# untitled_wifi.net
KiCad netlist of a schematic drawn in EAGLE
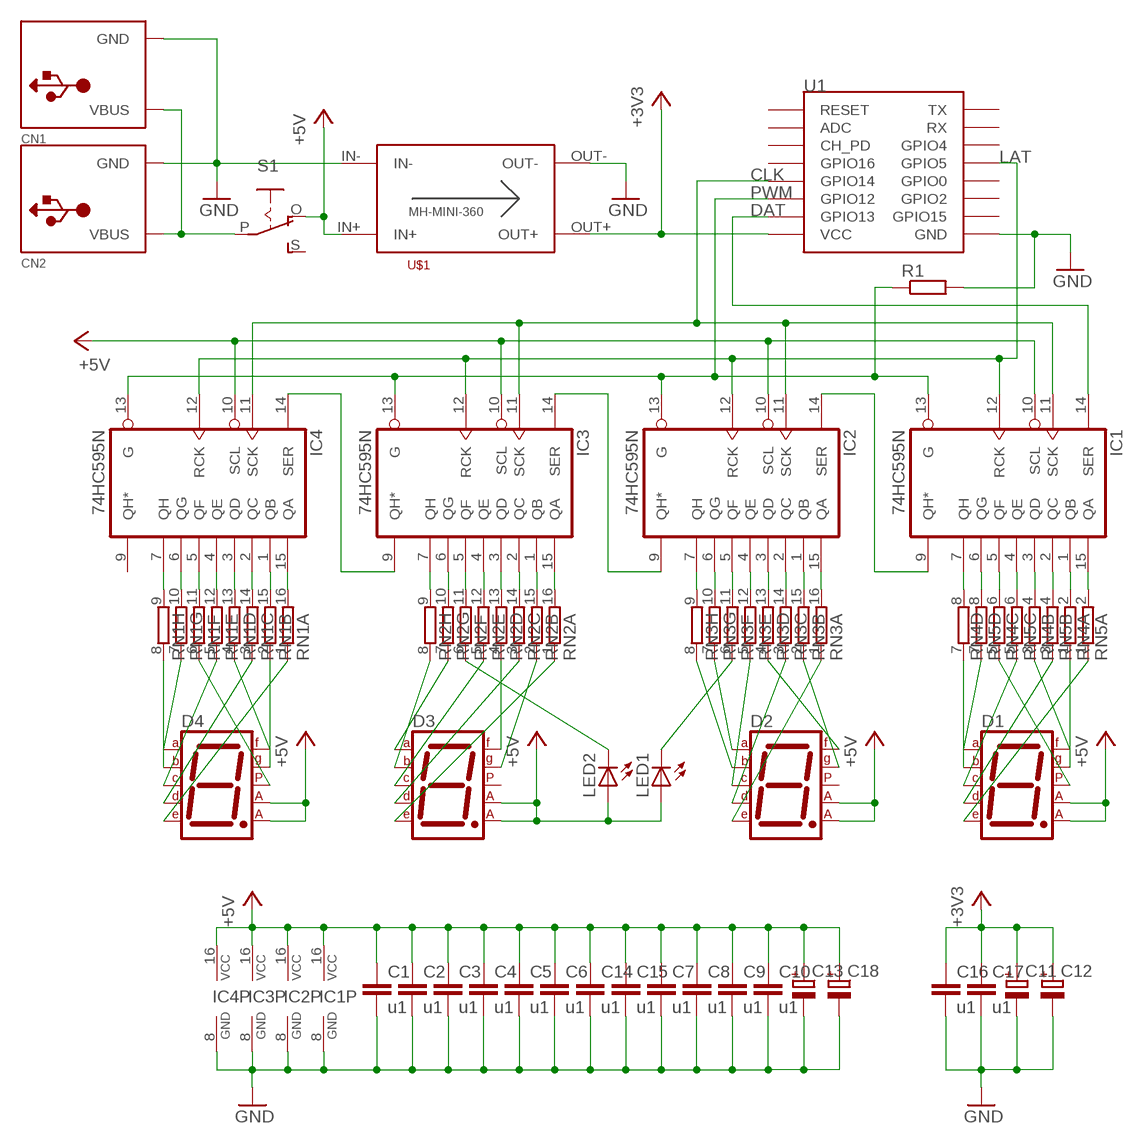
[diagram p0: schematic, sheet 1]

(export (version "E")
  (design (tool "Eeschema 10.0.6"))
  (components
    (comp (ref "C1")
      (value "u1")
      (footprint "eagle-import:C025-025X050")
      (libsource (lib "eagle-import") (part "C-EU025-025X050"))
    )
    (comp (ref "C2")
      (value "u1")
      (footprint "eagle-import:C025-025X050")
      (libsource (lib "eagle-import") (part "C-EU025-025X050"))
    )
    (comp (ref "C3")
      (value "u1")
      (footprint "eagle-import:C025-025X050")
      (libsource (lib "eagle-import") (part "C-EU025-025X050"))
    )
    (comp (ref "C4")
      (value "u1")
      (footprint "eagle-import:C025-025X050")
      (libsource (lib "eagle-import") (part "C-EU025-025X050"))
    )
    (comp (ref "C5")
      (value "u1")
      (footprint "eagle-import:C025-025X050")
      (libsource (lib "eagle-import") (part "C-EU025-025X050"))
    )
    (comp (ref "C6")
      (value "u1")
      (footprint "eagle-import:C025-025X050")
      (libsource (lib "eagle-import") (part "C-EU025-025X050"))
    )
    (comp (ref "C7")
      (value "u1")
      (footprint "eagle-import:C0805K")
      (libsource (lib "eagle-import") (part "C-EUC0805K"))
    )
    (comp (ref "C8")
      (value "u1")
      (footprint "eagle-import:C0805K")
      (libsource (lib "eagle-import") (part "C-EUC0805K"))
    )
    (comp (ref "C9")
      (value "u1")
      (footprint "eagle-import:C0805K")
      (libsource (lib "eagle-import") (part "C-EUC0805K"))
    )
    (comp (ref "C10")
      (value "u1")
      (footprint "eagle-import:C0805K")
      (libsource (lib "eagle-import") (part "C-EUC0805K"))
    )
    (comp (ref "C11")
      (value "CPOL-EUTT2D4L")
      (footprint "eagle-import:TT2D4L")
      (libsource (lib "eagle-import") (part "CPOL-EUTT2D4L"))
    )
    (comp (ref "C12")
      (value "CPOL-EUTT2D4L")
      (footprint "eagle-import:TT2D4L")
      (libsource (lib "eagle-import") (part "CPOL-EUTT2D4L"))
    )
    (comp (ref "C13")
      (value "CPOL-EUE2.5-7")
      (footprint "eagle-import:E2,5-7")
      (libsource (lib "eagle-import") (part "CPOL-EUE2.5-7"))
    )
    (comp (ref "C14")
      (value "u1")
      (footprint "eagle-import:C025-025X050")
      (libsource (lib "eagle-import") (part "C-EU025-025X050"))
    )
    (comp (ref "C15")
      (value "u1")
      (footprint "eagle-import:C025-025X050")
      (libsource (lib "eagle-import") (part "C-EU025-025X050"))
    )
    (comp (ref "C16")
      (value "u1")
      (footprint "eagle-import:C025-025X050")
      (libsource (lib "eagle-import") (part "C-EU025-025X050"))
    )
    (comp (ref "C17")
      (value "u1")
      (footprint "eagle-import:C025-025X050")
      (libsource (lib "eagle-import") (part "C-EU025-025X050"))
    )
    (comp (ref "C18")
      (value "CPOL-EUE2.5-7")
      (footprint "eagle-import:E2,5-7")
      (libsource (lib "eagle-import") (part "CPOL-EUE2.5-7"))
    )
    (comp (ref "CN1")
      (value "USBPWR-ONLY")
      (footprint "eagle-import:USB-MINIB-THM")
      (libsource (lib "eagle-import") (part "USBPWR-ONLY"))
    )
    (comp (ref "CN2")
      (value "USBPWR-ONLY")
      (footprint "eagle-import:USB-MINIB-THM")
      (libsource (lib "eagle-import") (part "USBPWR-ONLY"))
    )
    (comp (ref "D1")
      (value "7SEG-CA")
      (footprint "eagle-import:7SEG-13")
      (libsource (lib "eagle-import") (part "7SEG-CA"))
    )
    (comp (ref "D2")
      (value "7SEG-CA")
      (footprint "eagle-import:7SEG-13")
      (libsource (lib "eagle-import") (part "7SEG-CA"))
    )
    (comp (ref "D3")
      (value "7SEG-CA")
      (footprint "eagle-import:7SEG-13")
      (libsource (lib "eagle-import") (part "7SEG-CA"))
    )
    (comp (ref "D4")
      (value "7SEG-CA")
      (footprint "eagle-import:7SEG-13")
      (libsource (lib "eagle-import") (part "7SEG-CA"))
    )
    (comp (ref "IC1")
      (value "74HC595N")
      (footprint "eagle-import:DIL16")
      (libsource (lib "eagle-import") (part "74595NHC"))
    )
    (comp (ref "IC2")
      (value "74HC595N")
      (footprint "eagle-import:DIL16")
      (libsource (lib "eagle-import") (part "74595NHC"))
    )
    (comp (ref "IC3")
      (value "74HC595N")
      (footprint "eagle-import:DIL16")
      (libsource (lib "eagle-import") (part "74595NHC"))
    )
    (comp (ref "IC4")
      (value "74HC595N")
      (footprint "eagle-import:DIL16")
      (libsource (lib "eagle-import") (part "74595NHC"))
    )
    (comp (ref "LED1")
      (value "LED3MM")
      (footprint "eagle-import:LED3MM")
      (libsource (lib "eagle-import") (part "LED3MM"))
    )
    (comp (ref "LED2")
      (value "LED3MM")
      (footprint "eagle-import:LED3MM")
      (libsource (lib "eagle-import") (part "LED3MM"))
    )
    (comp (ref "R1")
      (value "R-EU_0204/7")
      (footprint "eagle-import:0204_7")
      (libsource (lib "eagle-import") (part "R-EU_0204/7"))
    )
    (comp (ref "RN1")
      (value "8R-N")
      (footprint "eagle-import:DIL16")
      (libsource (lib "eagle-import") (part "8R-N"))
    )
    (comp (ref "RN2")
      (value "8R-N")
      (footprint "eagle-import:DIL16")
      (libsource (lib "eagle-import") (part "8R-N"))
    )
    (comp (ref "RN3")
      (value "8R-N")
      (footprint "eagle-import:DIL16")
      (libsource (lib "eagle-import") (part "8R-N"))
    )
    (comp (ref "RN4")
      (value "E4R")
      (footprint "eagle-import:SIL8")
      (libsource (lib "eagle-import") (part "E4R"))
    )
    (comp (ref "RN5")
      (value "E4R")
      (footprint "eagle-import:SIL8")
      (libsource (lib "eagle-import") (part "E4R"))
    )
    (comp (ref "S1")
      (value "EG1218S")
      (footprint "eagle-import:EG1218")
      (libsource (lib "eagle-import") (part "EG1218S"))
    )
    (comp (ref "U$1")
      (value "DC-DC_CONV_MINISTD")
      (footprint "eagle-import:DC-DC_CONV_MINI")
      (libsource (lib "eagle-import") (part "DC-DC_CONV_MINISTD"))
    )
    (comp (ref "U1")
      (value "ESP12EDIP")
      (footprint "eagle-import:ESP-12-BREAKOUT")
      (libsource (lib "eagle-import") (part "ESP12EDIP"))
    )
  )
  (nets
    (net (code "1") (name "+3V3") (class "Default")
      (node (ref "C11") (pin "+") (pinfunction "+_+") (pintype "passive"))
      (node (ref "C12") (pin "+") (pinfunction "+_+") (pintype "passive"))
      (node (ref "C16") (pin "1") (pinfunction "1_1") (pintype "passive"))
      (node (ref "C17") (pin "1") (pinfunction "1_1") (pintype "passive"))
      (node (ref "U$1") (pin "OUT+") (pinfunction "OUT+_OUT+") (pintype "bidirectional"))
      (node (ref "U1") (pin "P$1") (pinfunction "VCC_P$1") (pintype "bidirectional"))
    )
    (net (code "2") (name "+5V") (class "Default")
      (node (ref "C1") (pin "1") (pinfunction "1_1") (pintype "passive"))
      (node (ref "C10") (pin "1") (pinfunction "1_1") (pintype "passive"))
      (node (ref "C13") (pin "+") (pinfunction "+_+") (pintype "passive"))
      (node (ref "C14") (pin "1") (pinfunction "1_1") (pintype "passive"))
      (node (ref "C15") (pin "1") (pinfunction "1_1") (pintype "passive"))
      (node (ref "C18") (pin "+") (pinfunction "+_+") (pintype "passive"))
      (node (ref "C2") (pin "1") (pinfunction "1_1") (pintype "passive"))
      (node (ref "C3") (pin "1") (pinfunction "1_1") (pintype "passive"))
      (node (ref "C4") (pin "1") (pinfunction "1_1") (pintype "passive"))
      (node (ref "C5") (pin "1") (pinfunction "1_1") (pintype "passive"))
      (node (ref "C6") (pin "1") (pinfunction "1_1") (pintype "passive"))
      (node (ref "C7") (pin "1") (pinfunction "1_1") (pintype "passive"))
      (node (ref "C8") (pin "1") (pinfunction "1_1") (pintype "passive"))
      (node (ref "C9") (pin "1") (pinfunction "1_1") (pintype "passive"))
      (node (ref "D1") (pin "3") (pinfunction "CA1_3") (pintype "passive"))
      (node (ref "D1") (pin "8") (pinfunction "CA2_8") (pintype "passive"))
      (node (ref "D2") (pin "3") (pinfunction "CA1_3") (pintype "passive"))
      (node (ref "D2") (pin "8") (pinfunction "CA2_8") (pintype "passive"))
      (node (ref "D3") (pin "3") (pinfunction "CA1_3") (pintype "passive"))
      (node (ref "D3") (pin "8") (pinfunction "CA2_8") (pintype "passive"))
      (node (ref "D4") (pin "3") (pinfunction "CA1_3") (pintype "passive"))
      (node (ref "D4") (pin "8") (pinfunction "CA2_8") (pintype "passive"))
      (node (ref "IC1") (pin "10") (pinfunction "SCL_10") (pintype "input"))
      (node (ref "IC1") (pin "16") (pinfunction "VCC_16") (pintype "power_in"))
      (node (ref "IC2") (pin "10") (pinfunction "SCL_10") (pintype "input"))
      (node (ref "IC2") (pin "16") (pinfunction "VCC_16") (pintype "power_in"))
      (node (ref "IC3") (pin "10") (pinfunction "SCL_10") (pintype "input"))
      (node (ref "IC3") (pin "16") (pinfunction "VCC_16") (pintype "power_in"))
      (node (ref "IC4") (pin "10") (pinfunction "SCL_10") (pintype "input"))
      (node (ref "IC4") (pin "16") (pinfunction "VCC_16") (pintype "power_in"))
      (node (ref "LED1") (pin "A") (pinfunction "A_A") (pintype "passive"))
      (node (ref "LED2") (pin "A") (pinfunction "A_A") (pintype "passive"))
      (node (ref "S1") (pin "O") (pinfunction "O_O") (pintype "passive"))
      (node (ref "U$1") (pin "IN+") (pinfunction "IN+_IN+") (pintype "bidirectional"))
    )
    (net (code "3") (name "/CLK") (class "Default")
      (node (ref "IC1") (pin "11") (pinfunction "SCK_11") (pintype "input"))
      (node (ref "IC2") (pin "11") (pinfunction "SCK_11") (pintype "input"))
      (node (ref "IC3") (pin "11") (pinfunction "SCK_11") (pintype "input"))
      (node (ref "IC4") (pin "11") (pinfunction "SCK_11") (pintype "input"))
      (node (ref "U1") (pin "P$4") (pinfunction "GPIO14_P$4") (pintype "bidirectional"))
    )
    (net (code "4") (name "/DAT") (class "Default")
      (node (ref "IC1") (pin "14") (pinfunction "SER_14") (pintype "input"))
      (node (ref "U1") (pin "P$2") (pinfunction "GPIO13_P$2") (pintype "bidirectional"))
    )
    (net (code "5") (name "/LAT") (class "Default")
      (node (ref "IC1") (pin "12") (pinfunction "RCK_12") (pintype "input"))
      (node (ref "IC2") (pin "12") (pinfunction "RCK_12") (pintype "input"))
      (node (ref "IC3") (pin "12") (pinfunction "RCK_12") (pintype "input"))
      (node (ref "IC4") (pin "12") (pinfunction "RCK_12") (pintype "input"))
      (node (ref "U1") (pin "P$13") (pinfunction "GPIO5_P$13") (pintype "bidirectional"))
    )
    (net (code "6") (name "/PWM") (class "Default")
      (node (ref "IC1") (pin "13") (pinfunction "G_13") (pintype "input"))
      (node (ref "IC2") (pin "13") (pinfunction "G_13") (pintype "input"))
      (node (ref "IC3") (pin "13") (pinfunction "G_13") (pintype "input"))
      (node (ref "IC4") (pin "13") (pinfunction "G_13") (pintype "input"))
      (node (ref "R1") (pin "1") (pinfunction "1_1") (pintype "passive"))
      (node (ref "U1") (pin "P$3") (pinfunction "GPIO12_P$3") (pintype "bidirectional"))
    )
    (net (code "7") (name "GND") (class "Default")
      (node (ref "C1") (pin "2") (pinfunction "2_2") (pintype "passive"))
      (node (ref "C10") (pin "2") (pinfunction "2_2") (pintype "passive"))
      (node (ref "C11") (pin "-") (pinfunction "-_-") (pintype "passive"))
      (node (ref "C12") (pin "-") (pinfunction "-_-") (pintype "passive"))
      (node (ref "C13") (pin "-") (pinfunction "-_-") (pintype "passive"))
      (node (ref "C14") (pin "2") (pinfunction "2_2") (pintype "passive"))
      (node (ref "C15") (pin "2") (pinfunction "2_2") (pintype "passive"))
      (node (ref "C16") (pin "2") (pinfunction "2_2") (pintype "passive"))
      (node (ref "C17") (pin "2") (pinfunction "2_2") (pintype "passive"))
      (node (ref "C18") (pin "-") (pinfunction "-_-") (pintype "passive"))
      (node (ref "C2") (pin "2") (pinfunction "2_2") (pintype "passive"))
      (node (ref "C3") (pin "2") (pinfunction "2_2") (pintype "passive"))
      (node (ref "C4") (pin "2") (pinfunction "2_2") (pintype "passive"))
      (node (ref "C5") (pin "2") (pinfunction "2_2") (pintype "passive"))
      (node (ref "C6") (pin "2") (pinfunction "2_2") (pintype "passive"))
      (node (ref "C7") (pin "2") (pinfunction "2_2") (pintype "passive"))
      (node (ref "C8") (pin "2") (pinfunction "2_2") (pintype "passive"))
      (node (ref "C9") (pin "2") (pinfunction "2_2") (pintype "passive"))
      (node (ref "CN1") (pin "GND") (pinfunction "GND_GND") (pintype "power_in"))
      (node (ref "CN1") (pin "GND1") (pinfunction "GND_GND1") (pintype "power_in"))
      (node (ref "CN1") (pin "GND2") (pinfunction "GND_GND2") (pintype "power_in"))
      (node (ref "CN1") (pin "GND3") (pinfunction "GND_GND3") (pintype "power_in"))
      (node (ref "CN1") (pin "GND4") (pinfunction "GND_GND4") (pintype "power_in"))
      (node (ref "CN2") (pin "GND") (pinfunction "GND_GND") (pintype "power_in"))
      (node (ref "CN2") (pin "GND1") (pinfunction "GND_GND1") (pintype "power_in"))
      (node (ref "CN2") (pin "GND2") (pinfunction "GND_GND2") (pintype "power_in"))
      (node (ref "CN2") (pin "GND3") (pinfunction "GND_GND3") (pintype "power_in"))
      (node (ref "CN2") (pin "GND4") (pinfunction "GND_GND4") (pintype "power_in"))
      (node (ref "IC1") (pin "8") (pinfunction "GND_8") (pintype "power_in"))
      (node (ref "IC2") (pin "8") (pinfunction "GND_8") (pintype "power_in"))
      (node (ref "IC3") (pin "8") (pinfunction "GND_8") (pintype "power_in"))
      (node (ref "IC4") (pin "8") (pinfunction "GND_8") (pintype "power_in"))
      (node (ref "R1") (pin "2") (pinfunction "2_2") (pintype "passive"))
      (node (ref "U$1") (pin "IN-") (pinfunction "IN-_IN-") (pintype "bidirectional"))
      (node (ref "U$1") (pin "OUT-") (pinfunction "OUT-_OUT-") (pintype "bidirectional"))
      (node (ref "U1") (pin "P$9") (pinfunction "GND_P$9") (pintype "bidirectional"))
    )
    (net (code "8") (name "Net-(CN1-PadVBUS)") (class "Default")
      (node (ref "CN1") (pin "VBUS") (pinfunction "VBUS_VBUS") (pintype "power_in"))
      (node (ref "CN2") (pin "VBUS") (pinfunction "VBUS_VBUS") (pintype "power_in"))
      (node (ref "S1") (pin "P") (pinfunction "P_P") (pintype "passive"))
    )
    (net (code "9") (name "Net-(D1-A)") (class "Default")
      (node (ref "D1") (pin "7") (pinfunction "A_7") (pintype "passive"))
      (node (ref "RN5") (pin "7") (pinfunction "1_7") (pintype "passive"))
    )
    (net (code "10") (name "Net-(D1-B)") (class "Default")
      (node (ref "D1") (pin "6") (pinfunction "B_6") (pintype "passive"))
      (node (ref "RN4") (pin "7") (pinfunction "1_7") (pintype "passive"))
    )
    (net (code "11") (name "Net-(D1-C)") (class "Default")
      (node (ref "D1") (pin "4") (pinfunction "C_4") (pintype "passive"))
      (node (ref "RN5") (pin "5") (pinfunction "1_5") (pintype "passive"))
    )
    (net (code "12") (name "Net-(D1-D)") (class "Default")
      (node (ref "D1") (pin "2") (pinfunction "D_2") (pintype "passive"))
      (node (ref "RN5") (pin "3") (pinfunction "1_3") (pintype "passive"))
    )
    (net (code "13") (name "Net-(D1-DP)") (class "Default")
      (node (ref "D1") (pin "5") (pinfunction "DP_5") (pintype "passive"))
      (node (ref "RN4") (pin "5") (pinfunction "1_5") (pintype "passive"))
    )
    (net (code "14") (name "Net-(D1-E)") (class "Default")
      (node (ref "D1") (pin "1") (pinfunction "E_1") (pintype "passive"))
      (node (ref "RN5") (pin "1") (pinfunction "1_1") (pintype "passive"))
    )
    (net (code "15") (name "Net-(D1-F)") (class "Default")
      (node (ref "D1") (pin "9") (pinfunction "F_9") (pintype "passive"))
      (node (ref "RN4") (pin "3") (pinfunction "1_3") (pintype "passive"))
    )
    (net (code "16") (name "Net-(D1-G)") (class "Default")
      (node (ref "D1") (pin "10") (pinfunction "G_10") (pintype "passive"))
      (node (ref "RN4") (pin "1") (pinfunction "1_1") (pintype "passive"))
    )
    (net (code "17") (name "Net-(D2-A)") (class "Default")
      (node (ref "D2") (pin "7") (pinfunction "A_7") (pintype "passive"))
      (node (ref "RN3") (pin "7") (pinfunction "1_7") (pintype "passive"))
    )
    (net (code "18") (name "Net-(D2-B)") (class "Default")
      (node (ref "D2") (pin "6") (pinfunction "B_6") (pintype "passive"))
      (node (ref "RN3") (pin "8") (pinfunction "1_8") (pintype "passive"))
    )
    (net (code "19") (name "Net-(D2-C)") (class "Default")
      (node (ref "D2") (pin "4") (pinfunction "C_4") (pintype "passive"))
      (node (ref "RN3") (pin "5") (pinfunction "1_5") (pintype "passive"))
    )
    (net (code "20") (name "Net-(D2-D)") (class "Default")
      (node (ref "D2") (pin "2") (pinfunction "D_2") (pintype "passive"))
      (node (ref "RN3") (pin "3") (pinfunction "1_3") (pintype "passive"))
    )
    (net (code "21") (name "Net-(D2-E)") (class "Default")
      (node (ref "D2") (pin "1") (pinfunction "E_1") (pintype "passive"))
      (node (ref "RN3") (pin "1") (pinfunction "1_1") (pintype "passive"))
    )
    (net (code "22") (name "Net-(D2-F)") (class "Default")
      (node (ref "D2") (pin "9") (pinfunction "F_9") (pintype "passive"))
      (node (ref "RN3") (pin "4") (pinfunction "1_4") (pintype "passive"))
    )
    (net (code "23") (name "Net-(D2-G)") (class "Default")
      (node (ref "D2") (pin "10") (pinfunction "G_10") (pintype "passive"))
      (node (ref "RN3") (pin "2") (pinfunction "1_2") (pintype "passive"))
    )
    (net (code "24") (name "Net-(D3-A)") (class "Default")
      (node (ref "D3") (pin "7") (pinfunction "A_7") (pintype "passive"))
      (node (ref "RN2") (pin "7") (pinfunction "1_7") (pintype "passive"))
    )
    (net (code "25") (name "Net-(D3-B)") (class "Default")
      (node (ref "D3") (pin "6") (pinfunction "B_6") (pintype "passive"))
      (node (ref "RN2") (pin "8") (pinfunction "1_8") (pintype "passive"))
    )
    (net (code "26") (name "Net-(D3-C)") (class "Default")
      (node (ref "D3") (pin "4") (pinfunction "C_4") (pintype "passive"))
      (node (ref "RN2") (pin "5") (pinfunction "1_5") (pintype "passive"))
    )
    (net (code "27") (name "Net-(D3-D)") (class "Default")
      (node (ref "D3") (pin "2") (pinfunction "D_2") (pintype "passive"))
      (node (ref "RN2") (pin "3") (pinfunction "1_3") (pintype "passive"))
    )
    (net (code "28") (name "Net-(D3-E)") (class "Default")
      (node (ref "D3") (pin "1") (pinfunction "E_1") (pintype "passive"))
      (node (ref "RN2") (pin "1") (pinfunction "1_1") (pintype "passive"))
    )
    (net (code "29") (name "Net-(D3-F)") (class "Default")
      (node (ref "D3") (pin "9") (pinfunction "F_9") (pintype "passive"))
      (node (ref "RN2") (pin "4") (pinfunction "1_4") (pintype "passive"))
    )
    (net (code "30") (name "Net-(D3-G)") (class "Default")
      (node (ref "D3") (pin "10") (pinfunction "G_10") (pintype "passive"))
      (node (ref "RN2") (pin "2") (pinfunction "1_2") (pintype "passive"))
    )
    (net (code "31") (name "Net-(D4-A)") (class "Default")
      (node (ref "D4") (pin "7") (pinfunction "A_7") (pintype "passive"))
      (node (ref "RN1") (pin "7") (pinfunction "1_7") (pintype "passive"))
    )
    (net (code "32") (name "Net-(D4-B)") (class "Default")
      (node (ref "D4") (pin "6") (pinfunction "B_6") (pintype "passive"))
      (node (ref "RN1") (pin "8") (pinfunction "1_8") (pintype "passive"))
    )
    (net (code "33") (name "Net-(D4-C)") (class "Default")
      (node (ref "D4") (pin "4") (pinfunction "C_4") (pintype "passive"))
      (node (ref "RN1") (pin "5") (pinfunction "1_5") (pintype "passive"))
    )
    (net (code "34") (name "Net-(D4-D)") (class "Default")
      (node (ref "D4") (pin "2") (pinfunction "D_2") (pintype "passive"))
      (node (ref "RN1") (pin "3") (pinfunction "1_3") (pintype "passive"))
    )
    (net (code "35") (name "Net-(D4-DP)") (class "Default")
      (node (ref "D4") (pin "5") (pinfunction "DP_5") (pintype "passive"))
      (node (ref "RN1") (pin "6") (pinfunction "1_6") (pintype "passive"))
    )
    (net (code "36") (name "Net-(D4-E)") (class "Default")
      (node (ref "D4") (pin "1") (pinfunction "E_1") (pintype "passive"))
      (node (ref "RN1") (pin "1") (pinfunction "1_1") (pintype "passive"))
    )
    (net (code "37") (name "Net-(D4-F)") (class "Default")
      (node (ref "D4") (pin "9") (pinfunction "F_9") (pintype "passive"))
      (node (ref "RN1") (pin "4") (pinfunction "1_4") (pintype "passive"))
    )
    (net (code "38") (name "Net-(D4-G)") (class "Default")
      (node (ref "D4") (pin "10") (pinfunction "G_10") (pintype "passive"))
      (node (ref "RN1") (pin "2") (pinfunction "1_2") (pintype "passive"))
    )
    (net (code "39") (name "Net-(IC1A-QA)") (class "Default")
      (node (ref "IC1") (pin "15") (pinfunction "QA_15") (pintype "tri_state"))
      (node (ref "RN5") (pin "2") (pinfunction "2_2") (pintype "passive"))
    )
    (net (code "40") (name "Net-(IC1A-QB)") (class "Default")
      (node (ref "IC1") (pin "1") (pinfunction "QB_1") (pintype "tri_state"))
      (node (ref "RN4") (pin "2") (pinfunction "2_2") (pintype "passive"))
    )
    (net (code "41") (name "Net-(IC1A-QC)") (class "Default")
      (node (ref "IC1") (pin "2") (pinfunction "QC_2") (pintype "tri_state"))
      (node (ref "RN5") (pin "4") (pinfunction "2_4") (pintype "passive"))
    )
    (net (code "42") (name "Net-(IC1A-QD)") (class "Default")
      (node (ref "IC1") (pin "3") (pinfunction "QD_3") (pintype "tri_state"))
      (node (ref "RN4") (pin "4") (pinfunction "2_4") (pintype "passive"))
    )
    (net (code "43") (name "Net-(IC1A-QE)") (class "Default")
      (node (ref "IC1") (pin "4") (pinfunction "QE_4") (pintype "tri_state"))
      (node (ref "RN5") (pin "6") (pinfunction "2_6") (pintype "passive"))
    )
    (net (code "44") (name "Net-(IC1A-QF)") (class "Default")
      (node (ref "IC1") (pin "5") (pinfunction "QF_5") (pintype "tri_state"))
      (node (ref "RN4") (pin "6") (pinfunction "2_6") (pintype "passive"))
    )
    (net (code "45") (name "Net-(IC1A-QG)") (class "Default")
      (node (ref "IC1") (pin "6") (pinfunction "QG_6") (pintype "tri_state"))
      (node (ref "RN5") (pin "8") (pinfunction "2_8") (pintype "passive"))
    )
    (net (code "46") (name "Net-(IC1A-QH)") (class "Default")
      (node (ref "IC1") (pin "7") (pinfunction "QH_7") (pintype "tri_state"))
      (node (ref "RN4") (pin "8") (pinfunction "2_8") (pintype "passive"))
    )
    (net (code "47") (name "Net-(IC1A-QH*)") (class "Default")
      (node (ref "IC1") (pin "9") (pinfunction "QH*_9") (pintype "tri_state"))
      (node (ref "IC2") (pin "14") (pinfunction "SER_14") (pintype "input"))
    )
    (net (code "48") (name "Net-(IC2A-QA)") (class "Default")
      (node (ref "IC2") (pin "15") (pinfunction "QA_15") (pintype "tri_state"))
      (node (ref "RN3") (pin "16") (pinfunction "2_16") (pintype "passive"))
    )
    (net (code "49") (name "Net-(IC2A-QB)") (class "Default")
      (node (ref "IC2") (pin "1") (pinfunction "QB_1") (pintype "tri_state"))
      (node (ref "RN3") (pin "15") (pinfunction "2_15") (pintype "passive"))
    )
    (net (code "50") (name "Net-(IC2A-QC)") (class "Default")
      (node (ref "IC2") (pin "2") (pinfunction "QC_2") (pintype "tri_state"))
      (node (ref "RN3") (pin "14") (pinfunction "2_14") (pintype "passive"))
    )
    (net (code "51") (name "Net-(IC2A-QD)") (class "Default")
      (node (ref "IC2") (pin "3") (pinfunction "QD_3") (pintype "tri_state"))
      (node (ref "RN3") (pin "13") (pinfunction "2_13") (pintype "passive"))
    )
    (net (code "52") (name "Net-(IC2A-QE)") (class "Default")
      (node (ref "IC2") (pin "4") (pinfunction "QE_4") (pintype "tri_state"))
      (node (ref "RN3") (pin "12") (pinfunction "2_12") (pintype "passive"))
    )
    (net (code "53") (name "Net-(IC2A-QF)") (class "Default")
      (node (ref "IC2") (pin "5") (pinfunction "QF_5") (pintype "tri_state"))
      (node (ref "RN3") (pin "11") (pinfunction "2_11") (pintype "passive"))
    )
    (net (code "54") (name "Net-(IC2A-QG)") (class "Default")
      (node (ref "IC2") (pin "6") (pinfunction "QG_6") (pintype "tri_state"))
      (node (ref "RN3") (pin "10") (pinfunction "2_10") (pintype "passive"))
    )
    (net (code "55") (name "Net-(IC2A-QH)") (class "Default")
      (node (ref "IC2") (pin "7") (pinfunction "QH_7") (pintype "tri_state"))
      (node (ref "RN3") (pin "9") (pinfunction "2_9") (pintype "passive"))
    )
    (net (code "56") (name "Net-(IC2A-QH*)") (class "Default")
      (node (ref "IC2") (pin "9") (pinfunction "QH*_9") (pintype "tri_state"))
      (node (ref "IC3") (pin "14") (pinfunction "SER_14") (pintype "input"))
    )
    (net (code "57") (name "Net-(IC3A-QA)") (class "Default")
      (node (ref "IC3") (pin "15") (pinfunction "QA_15") (pintype "tri_state"))
      (node (ref "RN2") (pin "16") (pinfunction "2_16") (pintype "passive"))
    )
    (net (code "58") (name "Net-(IC3A-QB)") (class "Default")
      (node (ref "IC3") (pin "1") (pinfunction "QB_1") (pintype "tri_state"))
      (node (ref "RN2") (pin "15") (pinfunction "2_15") (pintype "passive"))
    )
    (net (code "59") (name "Net-(IC3A-QC)") (class "Default")
      (node (ref "IC3") (pin "2") (pinfunction "QC_2") (pintype "tri_state"))
      (node (ref "RN2") (pin "14") (pinfunction "2_14") (pintype "passive"))
    )
    (net (code "60") (name "Net-(IC3A-QD)") (class "Default")
      (node (ref "IC3") (pin "3") (pinfunction "QD_3") (pintype "tri_state"))
      (node (ref "RN2") (pin "13") (pinfunction "2_13") (pintype "passive"))
    )
    (net (code "61") (name "Net-(IC3A-QE)") (class "Default")
      (node (ref "IC3") (pin "4") (pinfunction "QE_4") (pintype "tri_state"))
      (node (ref "RN2") (pin "12") (pinfunction "2_12") (pintype "passive"))
    )
    (net (code "62") (name "Net-(IC3A-QF)") (class "Default")
      (node (ref "IC3") (pin "5") (pinfunction "QF_5") (pintype "tri_state"))
      (node (ref "RN2") (pin "11") (pinfunction "2_11") (pintype "passive"))
    )
    (net (code "63") (name "Net-(IC3A-QG)") (class "Default")
      (node (ref "IC3") (pin "6") (pinfunction "QG_6") (pintype "tri_state"))
      (node (ref "RN2") (pin "10") (pinfunction "2_10") (pintype "passive"))
    )
    (net (code "64") (name "Net-(IC3A-QH)") (class "Default")
      (node (ref "IC3") (pin "7") (pinfunction "QH_7") (pintype "tri_state"))
      (node (ref "RN2") (pin "9") (pinfunction "2_9") (pintype "passive"))
    )
    (net (code "65") (name "Net-(IC3A-QH*)") (class "Default")
      (node (ref "IC3") (pin "9") (pinfunction "QH*_9") (pintype "tri_state"))
      (node (ref "IC4") (pin "14") (pinfunction "SER_14") (pintype "input"))
    )
    (net (code "66") (name "Net-(IC4A-QA)") (class "Default")
      (node (ref "IC4") (pin "15") (pinfunction "QA_15") (pintype "tri_state"))
      (node (ref "RN1") (pin "16") (pinfunction "2_16") (pintype "passive"))
    )
    (net (code "67") (name "Net-(IC4A-QB)") (class "Default")
      (node (ref "IC4") (pin "1") (pinfunction "QB_1") (pintype "tri_state"))
      (node (ref "RN1") (pin "15") (pinfunction "2_15") (pintype "passive"))
    )
    (net (code "68") (name "Net-(IC4A-QC)") (class "Default")
      (node (ref "IC4") (pin "2") (pinfunction "QC_2") (pintype "tri_state"))
      (node (ref "RN1") (pin "14") (pinfunction "2_14") (pintype "passive"))
    )
    (net (code "69") (name "Net-(IC4A-QD)") (class "Default")
      (node (ref "IC4") (pin "3") (pinfunction "QD_3") (pintype "tri_state"))
      (node (ref "RN1") (pin "13") (pinfunction "2_13") (pintype "passive"))
    )
    (net (code "70") (name "Net-(IC4A-QE)") (class "Default")
      (node (ref "IC4") (pin "4") (pinfunction "QE_4") (pintype "tri_state"))
      (node (ref "RN1") (pin "12") (pinfunction "2_12") (pintype "passive"))
    )
    (net (code "71") (name "Net-(IC4A-QF)") (class "Default")
      (node (ref "IC4") (pin "5") (pinfunction "QF_5") (pintype "tri_state"))
      (node (ref "RN1") (pin "11") (pinfunction "2_11") (pintype "passive"))
    )
    (net (code "72") (name "Net-(IC4A-QG)") (class "Default")
      (node (ref "IC4") (pin "6") (pinfunction "QG_6") (pintype "tri_state"))
      (node (ref "RN1") (pin "10") (pinfunction "2_10") (pintype "passive"))
    )
    (net (code "73") (name "Net-(IC4A-QH)") (class "Default")
      (node (ref "IC4") (pin "7") (pinfunction "QH_7") (pintype "tri_state"))
      (node (ref "RN1") (pin "9") (pinfunction "2_9") (pintype "passive"))
    )
    (net (code "74") (name "Net-(LED1-C)") (class "Default")
      (node (ref "LED1") (pin "K") (pinfunction "C_K") (pintype "passive"))
      (node (ref "RN3") (pin "6") (pinfunction "1_6") (pintype "passive"))
    )
    (net (code "75") (name "Net-(LED2-C)") (class "Default")
      (node (ref "LED2") (pin "K") (pinfunction "C_K") (pintype "passive"))
      (node (ref "RN2") (pin "6") (pinfunction "1_6") (pintype "passive"))
    )
    (net (code "76") (name "unconnected-(D2-DP-Pad5)") (class "Default")
      (node (ref "D2") (pin "5") (pinfunction "DP_5") (pintype "passive"))
    )
    (net (code "77") (name "unconnected-(D3-DP-Pad5)") (class "Default")
      (node (ref "D3") (pin "5") (pinfunction "DP_5") (pintype "passive"))
    )
    (net (code "78") (name "unconnected-(IC4A-QH*-Pad9)") (class "Default")
      (node (ref "IC4") (pin "9") (pinfunction "QH*_9") (pintype "tri_state"))
    )
    (net (code "79") (name "unconnected-(S1-PadS)") (class "Default")
      (node (ref "S1") (pin "S") (pinfunction "S_S") (pintype "passive"))
    )
    (net (code "80") (name "unconnected-(U1-ADC-PadP$7)") (class "Default")
      (node (ref "U1") (pin "P$7") (pinfunction "ADC_P$7") (pintype "bidirectional"))
    )
    (net (code "81") (name "unconnected-(U1-CH_PD-PadP$6)") (class "Default")
      (node (ref "U1") (pin "P$6") (pinfunction "CH_PD_P$6") (pintype "bidirectional"))
    )
    (net (code "82") (name "unconnected-(U1-GPIO0-PadP$12)") (class "Default")
      (node (ref "U1") (pin "P$12") (pinfunction "GPIO0_P$12") (pintype "bidirectional"))
    )
    (net (code "83") (name "unconnected-(U1-GPIO2-PadP$11)") (class "Default")
      (node (ref "U1") (pin "P$11") (pinfunction "GPIO2_P$11") (pintype "bidirectional"))
    )
    (net (code "84") (name "unconnected-(U1-GPIO4-PadP$14)") (class "Default")
      (node (ref "U1") (pin "P$14") (pinfunction "GPIO4_P$14") (pintype "bidirectional"))
    )
    (net (code "85") (name "unconnected-(U1-GPIO15-PadP$10)") (class "Default")
      (node (ref "U1") (pin "P$10") (pinfunction "GPIO15_P$10") (pintype "bidirectional"))
    )
    (net (code "86") (name "unconnected-(U1-GPIO16-PadP$5)") (class "Default")
      (node (ref "U1") (pin "P$5") (pinfunction "GPIO16_P$5") (pintype "bidirectional"))
    )
    (net (code "87") (name "unconnected-(U1-RESET-PadP$8)") (class "Default")
      (node (ref "U1") (pin "P$8") (pinfunction "RESET_P$8") (pintype "bidirectional"))
    )
    (net (code "88") (name "unconnected-(U1-RX-PadP$15)") (class "Default")
      (node (ref "U1") (pin "P$15") (pinfunction "RX_P$15") (pintype "bidirectional"))
    )
    (net (code "89") (name "unconnected-(U1-TX-PadP$16)") (class "Default")
      (node (ref "U1") (pin "P$16") (pinfunction "TX_P$16") (pintype "bidirectional"))
    )
  )
)
